# Mother_Board_IMU.net
KiCad netlist of a schematic drawn in Altium Designer
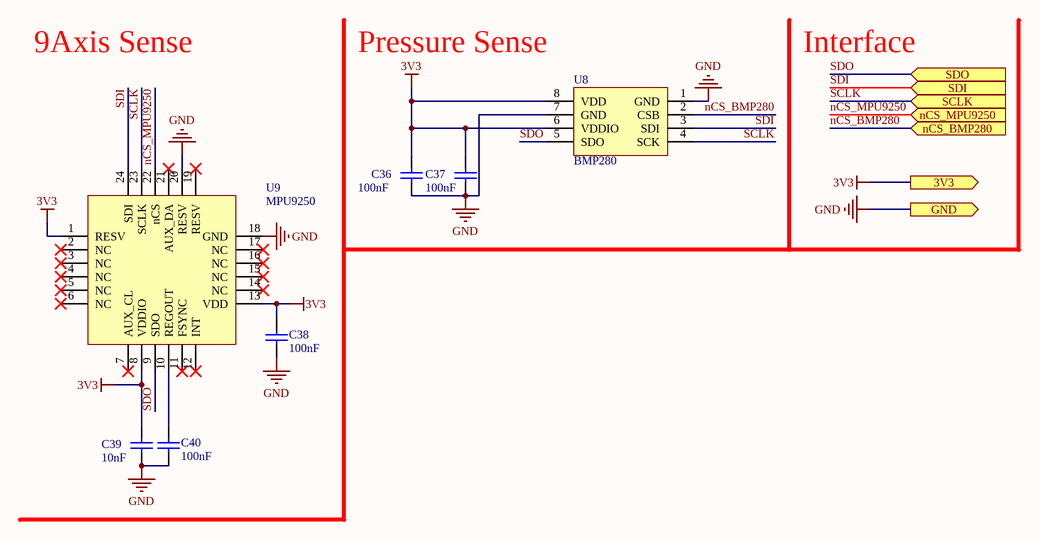
[diagram p0: Mother Board IMU.SchDoc]

(export (version "E")
  (design (tool "Eeschema 10.0.6"))
  (components
    (comp (ref "C36") (value "100nF") (footprint "C0603") (libsource (lib "Cap") (part "Cap")))
    (comp (ref "C37") (value "100nF") (footprint "C0603") (libsource (lib "Cap") (part "Cap")))
    (comp (ref "C38") (value "100nF") (footprint "C0603") (libsource (lib "Cap") (part "Cap")))
    (comp (ref "C39") (value "10nF") (footprint "C0603") (libsource (lib "Cap") (part "Cap")))
    (comp (ref "C40") (value "100nF") (footprint "C0603") (libsource (lib "Cap") (part "Cap")))
    (comp (ref "U8")
      (value "BMP280")
      (footprint "BMP280")
      (description "气压计")
      (libsource (lib "All lib") (part "BMP280"))
    )
    (comp (ref "U9")
      (value "MPU9250")
      (footprint "QFN24 3*3")
      (description "9轴 加速度 角速度 地磁传感器")
      (libsource (lib "All lib") (part "MPU9250"))
    )
  )
  (nets
    (net (code "1") (name "/SCLK") (class "Default")
      (node (ref "U8") (pin "4") (pinfunction "SCK_4") (pintype "passive"))
      (node (ref "U9") (pin "23") (pinfunction "SCLK_23") (pintype "passive"))
    )
    (net (code "2") (name "/SDI") (class "Default")
      (node (ref "U8") (pin "3") (pinfunction "SDI_3") (pintype "passive"))
      (node (ref "U9") (pin "24") (pinfunction "SDI_24") (pintype "passive"))
    )
    (net (code "3") (name "/SDO") (class "Default")
      (node (ref "U8") (pin "5") (pinfunction "SDO_5") (pintype "passive"))
      (node (ref "U9") (pin "9") (pinfunction "SDO_9") (pintype "passive"))
    )
    (net (code "4") (name "/nCS_BMP280") (class "Default")
      (node (ref "U8") (pin "2") (pinfunction "CSB_2") (pintype "passive"))
    )
    (net (code "5") (name "/nCS_MPU9250") (class "Default")
      (node (ref "U9") (pin "22") (pinfunction "nCS_22") (pintype "passive"))
    )
    (net (code "6") (name "3V3") (class "Default")
      (node (ref "C36") (pin "2") (pinfunction "2_2") (pintype "passive"))
      (node (ref "C37") (pin "2") (pinfunction "2_2") (pintype "passive"))
      (node (ref "C38") (pin "2") (pinfunction "2_2") (pintype "passive"))
      (node (ref "C39") (pin "2") (pinfunction "2_2") (pintype "passive"))
      (node (ref "U8") (pin "6") (pinfunction "VDDIO_6") (pintype "passive"))
      (node (ref "U8") (pin "8") (pinfunction "VDD_8") (pintype "passive"))
      (node (ref "U9") (pin "1") (pinfunction "RESV_1") (pintype "passive"))
      (node (ref "U9") (pin "13") (pinfunction "VDD_13") (pintype "passive"))
      (node (ref "U9") (pin "8") (pinfunction "VDDIO_8") (pintype "passive"))
    )
    (net (code "7") (name "GND") (class "Default")
      (node (ref "C36") (pin "1") (pinfunction "1_1") (pintype "passive"))
      (node (ref "C37") (pin "1") (pinfunction "1_1") (pintype "passive"))
      (node (ref "C38") (pin "1") (pinfunction "1_1") (pintype "passive"))
      (node (ref "C39") (pin "1") (pinfunction "1_1") (pintype "passive"))
      (node (ref "C40") (pin "1") (pinfunction "1_1") (pintype "passive"))
      (node (ref "U8") (pin "1") (pinfunction "GND_1") (pintype "passive"))
      (node (ref "U8") (pin "7") (pinfunction "GND_7") (pintype "passive"))
      (node (ref "U9") (pin "18") (pinfunction "GND_18") (pintype "passive"))
      (node (ref "U9") (pin "20") (pinfunction "RESV_20") (pintype "passive"))
    )
    (net (code "8") (name "Net-(U9-REGOUT)") (class "Default")
      (node (ref "C40") (pin "2") (pinfunction "2_2") (pintype "passive"))
      (node (ref "U9") (pin "10") (pinfunction "REGOUT_10") (pintype "passive"))
    )
    (net (code "9") (name "unconnected-(U9-AUX_CL-Pad7)") (class "Default")
      (node (ref "U9") (pin "7") (pinfunction "AUX_CL_7") (pintype "passive+no_connect"))
    )
    (net (code "10") (name "unconnected-(U9-AUX_DA-Pad21)") (class "Default")
      (node (ref "U9") (pin "21") (pinfunction "AUX_DA_21") (pintype "passive+no_connect"))
    )
    (net (code "11") (name "unconnected-(U9-FSYNC-Pad11)") (class "Default")
      (node (ref "U9") (pin "11") (pinfunction "FSYNC_11") (pintype "passive+no_connect"))
    )
    (net (code "12") (name "unconnected-(U9-INT-Pad12)") (class "Default")
      (node (ref "U9") (pin "12") (pinfunction "INT_12") (pintype "passive+no_connect"))
    )
    (net (code "13") (name "unconnected-(U9-NC-Pad2)") (class "Default")
      (node (ref "U9") (pin "2") (pinfunction "NC_2") (pintype "passive+no_connect"))
    )
    (net (code "14") (name "unconnected-(U9-NC-Pad3)") (class "Default")
      (node (ref "U9") (pin "3") (pinfunction "NC_3") (pintype "passive+no_connect"))
    )
    (net (code "15") (name "unconnected-(U9-NC-Pad4)") (class "Default")
      (node (ref "U9") (pin "4") (pinfunction "NC_4") (pintype "passive+no_connect"))
    )
    (net (code "16") (name "unconnected-(U9-NC-Pad5)") (class "Default")
      (node (ref "U9") (pin "5") (pinfunction "NC_5") (pintype "passive+no_connect"))
    )
    (net (code "17") (name "unconnected-(U9-NC-Pad6)") (class "Default")
      (node (ref "U9") (pin "6") (pinfunction "NC_6") (pintype "passive+no_connect"))
    )
    (net (code "18") (name "unconnected-(U9-NC-Pad14)") (class "Default")
      (node (ref "U9") (pin "14") (pinfunction "NC_14") (pintype "passive+no_connect"))
    )
    (net (code "19") (name "unconnected-(U9-NC-Pad15)") (class "Default")
      (node (ref "U9") (pin "15") (pinfunction "NC_15") (pintype "passive+no_connect"))
    )
    (net (code "20") (name "unconnected-(U9-NC-Pad16)") (class "Default")
      (node (ref "U9") (pin "16") (pinfunction "NC_16") (pintype "passive+no_connect"))
    )
    (net (code "21") (name "unconnected-(U9-NC-Pad17)") (class "Default")
      (node (ref "U9") (pin "17") (pinfunction "NC_17") (pintype "passive+no_connect"))
    )
    (net (code "22") (name "unconnected-(U9-RESV-Pad19)") (class "Default")
      (node (ref "U9") (pin "19") (pinfunction "RESV_19") (pintype "passive+no_connect"))
    )
  )
)
